# AFBR-TX-fiber_optic_transmiter_OPCn.net
KiCad netlist of a schematic drawn in Altium Designer
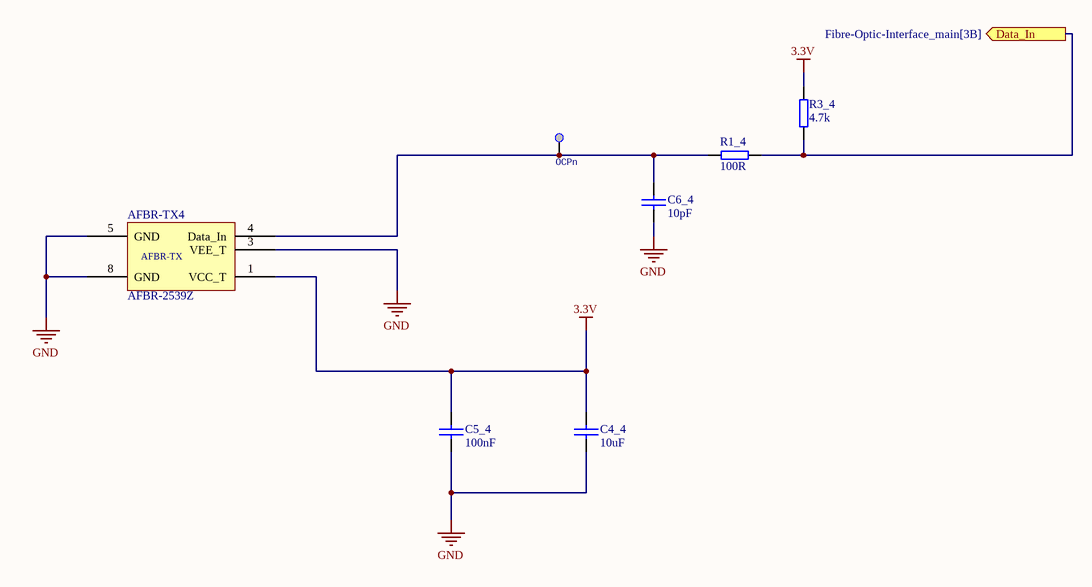
[diagram p0: AFBR-TX-fiber_optic_transmiter_OPCn.SchDoc]

(export (version "E")
  (design (tool "Eeschema 10.0.6"))
  (components
    (comp (ref "AFBR-TX4")
      (value "AFBR-2539Z")
      (footprint "AFBR-TX/RX-HORIZONTAL")
      (description "Fiber Optic Transmitters, Receivers, Transceivers VL V 50MBd RX inv")
      (libsource (lib "fibre_optic_transmiters") (part "AFBR-TX"))
    )
    (comp (ref "C4_4")
      (value "10uF")
      (footprint "1206")
      (description "Capacitor")
      (libsource (lib "passive_elements") (part "C_1"))
    )
    (comp (ref "C5_4")
      (value "100nF")
      (footprint "0603C")
      (description "Capacitor")
      (libsource (lib "passive_elements") (part "C"))
    )
    (comp (ref "C6_4")
      (value "10pF")
      (footprint "0603C")
      (description "Capacitor")
      (libsource (lib "passive_elements") (part "C_3"))
    )
    (comp (ref "OCPn")
      (value "PK_1")
      (footprint "PK")
      (description "Punkt")
      (libsource (lib "others") (part "PK_1"))
    )
    (comp (ref "R1_4") (value "100R") (footprint "0603R") (libsource (lib "passive_elements") (part "R_1")))
    (comp (ref "R3_4") (value "4.7k") (footprint "0603R") (libsource (lib "passive_elements") (part "R")))
  )
  (nets
    (net (code "1") (name "/Data_In") (class "Default")
      (node (ref "R1_4") (pin "2") (pinfunction "2_2") (pintype "passive"))
      (node (ref "R3_4") (pin "1") (pinfunction "1_1") (pintype "passive"))
    )
    (net (code "2") (name "3.3V") (class "Default")
      (node (ref "AFBR-TX4") (pin "1") (pinfunction "VCC_T_1") (pintype "passive"))
      (node (ref "C4_4") (pin "1") (pinfunction "1_1") (pintype "passive"))
      (node (ref "C5_4") (pin "1") (pinfunction "1_1") (pintype "passive"))
      (node (ref "R3_4") (pin "2") (pinfunction "2_2") (pintype "passive"))
    )
    (net (code "3") (name "GND") (class "Default")
      (node (ref "AFBR-TX4") (pin "3") (pinfunction "VEE_T_3") (pintype "passive"))
      (node (ref "AFBR-TX4") (pin "5") (pinfunction "GND_5") (pintype "passive"))
      (node (ref "AFBR-TX4") (pin "8") (pinfunction "GND_8") (pintype "passive"))
      (node (ref "C4_4") (pin "2") (pinfunction "2_2") (pintype "passive"))
      (node (ref "C5_4") (pin "2") (pinfunction "2_2") (pintype "passive"))
      (node (ref "C6_4") (pin "2") (pinfunction "2_2") (pintype "passive"))
    )
    (net (code "4") (name "Net-(AFBR-TX4-Data_In)") (class "Default")
      (node (ref "AFBR-TX4") (pin "4") (pinfunction "Data_In_4") (pintype "passive"))
      (node (ref "C6_4") (pin "1") (pinfunction "1_1") (pintype "passive"))
      (node (ref "OCPn") (pin "1") (pinfunction "1_1") (pintype "passive"))
      (node (ref "R1_4") (pin "1") (pinfunction "1_1") (pintype "passive"))
    )
  )
)
